# DXP.net
KiCad netlist of a schematic drawn in Altium Designer
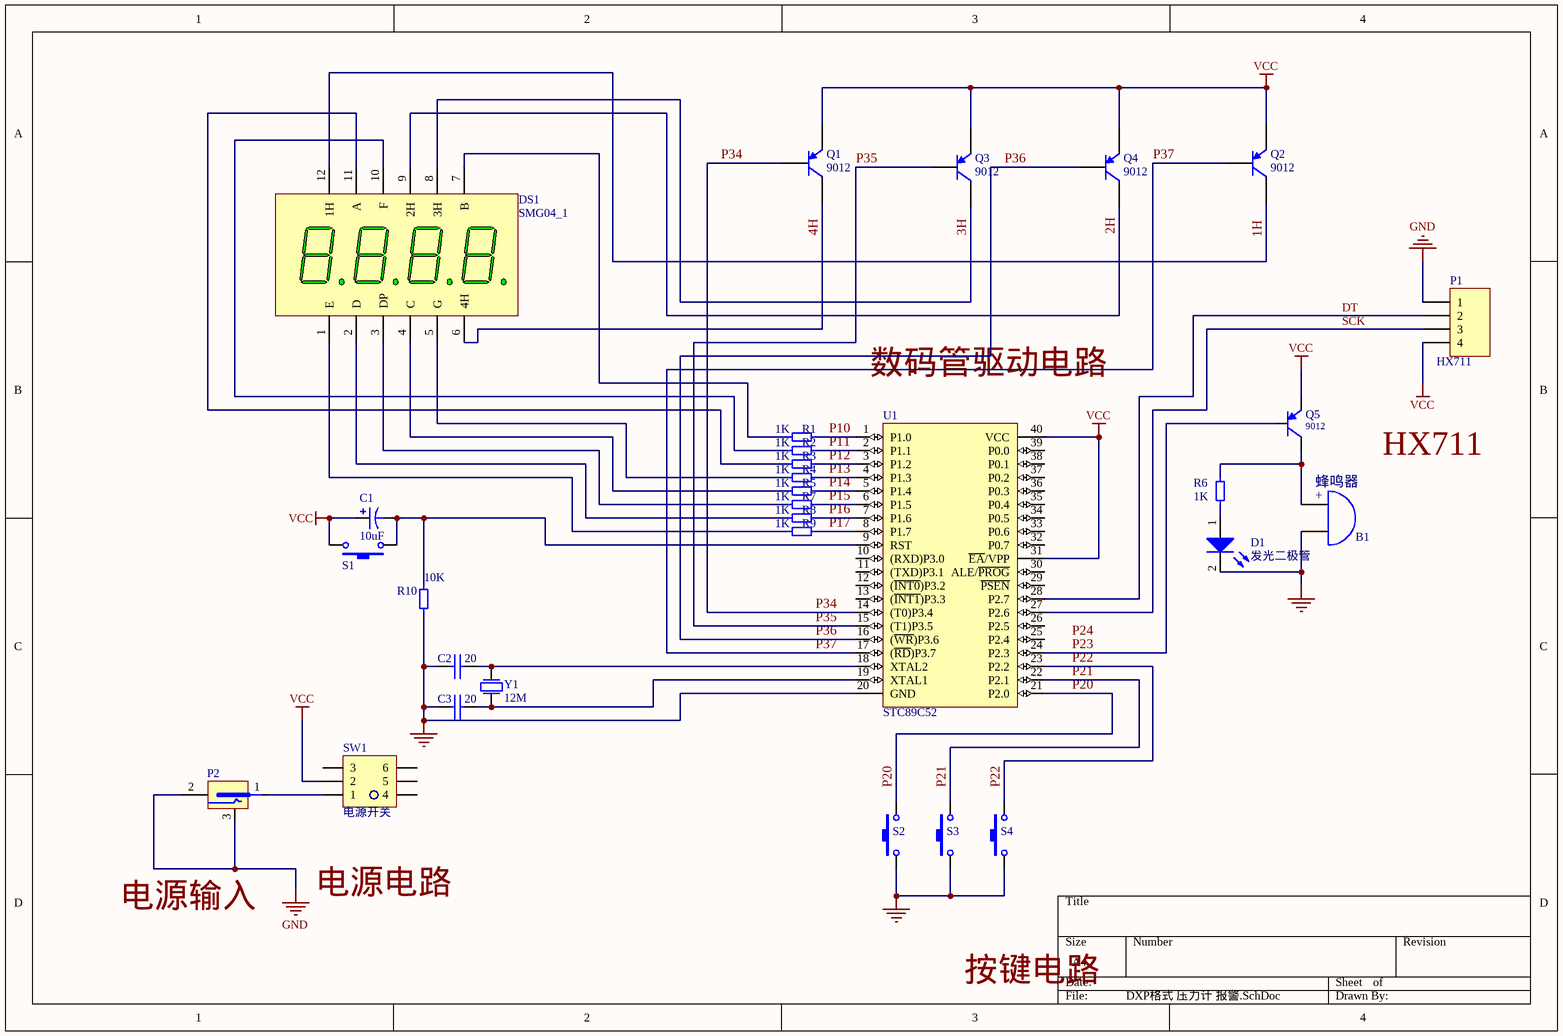
[diagram p0: DXP格式 压力计 报警.SchDoc]

(export (version "E")
  (design (tool "Eeschema 10.0.6"))
  (components
    (comp (ref "B1")
      (value "蜂鸣器")
      (footprint "Bett")
      (description "Bell")
      (libsource (lib "*") (part "BELL"))
    )
    (comp (ref "C1")
      (value "10uF")
      (footprint "C_10")
      (description "Polarized Capacitor (Radial)")
      (fields (field (name "PUBLISHER") "Altium Limited"))
      (libsource (lib "*") (part "Cap Pol1"))
    )
    (comp (ref "C2") (value "20") (footprint "CAP CP") (description "电容") (libsource (lib "*") (part "CAP")))
    (comp (ref "C3") (value "20") (footprint "CAP CP") (description "电容") (libsource (lib "*") (part "CAP")))
    (comp (ref "D1") (value "发光二极管") (footprint "LED直插") (libsource (lib "*") (part "D")))
    (comp (ref "DS1") (value "SMG04_1") (footprint "SMG04") (libsource (lib "*") (part "SMG04_1")))
    (comp (ref "P1")
      (value "HX711")
      (footprint "HX711")
      (description "Header, 4-Pin")
      (fields (field (name "PUBLISHER") "Altium Limited"))
      (libsource (lib "Miscellaneous Connectors") (part "Header 4"))
    )
    (comp (ref "P2") (value "电源输入") (footprint "DC2.1") (libsource (lib "我自己的") (part "POWER")))
    (comp (ref "Q1")
      (value "9012")
      (footprint "s三极管直插")
      (description "PNP General Purpose Amplifier")
      (fields (field (name "PUBLISHER") "Altium Limited"))
      (libsource (lib "*") (part "2N3906"))
    )
    (comp (ref "Q2")
      (value "9012")
      (footprint "s三极管直插")
      (description "PNP General Purpose Amplifier")
      (fields (field (name "PUBLISHER") "Altium Limited"))
      (libsource (lib "*") (part "2N3906"))
    )
    (comp (ref "Q3")
      (value "9012")
      (footprint "s三极管直插")
      (description "PNP General Purpose Amplifier")
      (fields (field (name "PUBLISHER") "Altium Limited"))
      (libsource (lib "*") (part "2N3906"))
    )
    (comp (ref "Q4")
      (value "9012")
      (footprint "s三极管直插")
      (description "PNP General Purpose Amplifier")
      (fields (field (name "PUBLISHER") "Altium Limited"))
      (libsource (lib "*") (part "2N3906"))
    )
    (comp (ref "Q5")
      (value "9012")
      (footprint "s三极管直插")
      (description "PNP General Purpose Amplifier")
      (fields (field (name "PUBLISHER") "Altium Limited"))
      (libsource (lib "") (part "2N3906_1"))
    )
    (comp (ref "R1") (value "1K") (footprint "AXIAL0.3") (libsource (lib "*") (part "RES2")))
    (comp (ref "R2") (value "1K") (footprint "AXIAL0.3") (libsource (lib "*") (part "RES2")))
    (comp (ref "R3") (value "1K") (footprint "AXIAL0.3") (libsource (lib "*") (part "RES2")))
    (comp (ref "R4") (value "1K") (footprint "AXIAL0.3") (libsource (lib "*") (part "RES2")))
    (comp (ref "R5") (value "1K") (footprint "AXIAL0.3") (libsource (lib "*") (part "RES2")))
    (comp (ref "R6") (value "1K") (footprint "AXIAL0.3") (libsource (lib "*") (part "RES2")))
    (comp (ref "R7") (value "1K") (footprint "AXIAL0.3") (libsource (lib "*") (part "RES2")))
    (comp (ref "R8") (value "1K") (footprint "AXIAL0.3") (libsource (lib "*") (part "RES2")))
    (comp (ref "R9") (value "1K") (footprint "AXIAL0.3") (libsource (lib "*") (part "RES2")))
    (comp (ref "R10") (value "10K") (footprint "AXIAL0.3") (libsource (lib "*") (part "RES2")))
    (comp (ref "S1")
      (value "SW-PB")
      (footprint "key")
      (description "Switch")
      (fields (field (name "PUBLISHER") "Altium Limited"))
      (libsource (lib "*") (part "SW-PB"))
    )
    (comp (ref "S2")
      (value "SW-PB")
      (footprint "key")
      (description "Switch")
      (fields (field (name "PUBLISHER") "Altium Limited"))
      (libsource (lib "*") (part "SW-PB"))
    )
    (comp (ref "S3")
      (value "SW-PB")
      (footprint "key")
      (description "Switch")
      (fields (field (name "PUBLISHER") "Altium Limited"))
      (libsource (lib "*") (part "SW-PB"))
    )
    (comp (ref "S4")
      (value "SW-PB")
      (footprint "key")
      (description "Switch")
      (fields (field (name "PUBLISHER") "Altium Limited"))
      (libsource (lib "*") (part "SW-PB"))
    )
    (comp (ref "SW1") (value "电源开关") (footprint "sw_自锁 1") (libsource (lib "我自己的") (part "SW1")))
    (comp (ref "U1") (value "STC89C52") (footprint "DIP40 - 做板") (libsource (lib "*") (part "U1")))
    (comp (ref "Y1")
      (value "12M")
      (footprint "XTAL")
      (description "Crystal Oscillator")
      (libsource (lib "*") (part "16M"))
    )
  )
  (nets
    (net (code "1") (name "/1H") (class "Default")
      (node (ref "DS1") (pin "12") (pinfunction "1H_12") (pintype "passive"))
      (node (ref "Q2") (pin "3") (pinfunction "C_3") (pintype "passive"))
    )
    (net (code "2") (name "/2H") (class "Default")
      (node (ref "DS1") (pin "9") (pinfunction "2H_9") (pintype "passive"))
      (node (ref "Q4") (pin "3") (pinfunction "C_3") (pintype "passive"))
    )
    (net (code "3") (name "/3H") (class "Default")
      (node (ref "DS1") (pin "8") (pinfunction "3H_8") (pintype "passive"))
      (node (ref "Q3") (pin "3") (pinfunction "C_3") (pintype "passive"))
    )
    (net (code "4") (name "/4H") (class "Default")
      (node (ref "DS1") (pin "6") (pinfunction "4H_6") (pintype "passive"))
      (node (ref "Q1") (pin "3") (pinfunction "C_3") (pintype "passive"))
    )
    (net (code "5") (name "/DT") (class "Default")
      (node (ref "P1") (pin "2") (pinfunction "2_2") (pintype "passive"))
      (node (ref "U1") (pin "28") (pinfunction "P2.7_28") (pintype "bidirectional"))
    )
    (net (code "7") (name "/P10") (class "Default")
      (node (ref "R1") (pin "2") (pinfunction "2_2") (pintype "passive"))
      (node (ref "U1") (pin "1") (pinfunction "P1.0_1") (pintype "bidirectional"))
    )
    (net (code "8") (name "/P11") (class "Default")
      (node (ref "R2") (pin "2") (pinfunction "2_2") (pintype "passive"))
      (node (ref "U1") (pin "2") (pinfunction "P1.1_2") (pintype "bidirectional"))
    )
    (net (code "9") (name "/P12") (class "Default")
      (node (ref "R3") (pin "2") (pinfunction "2_2") (pintype "passive"))
      (node (ref "U1") (pin "3") (pinfunction "P1.2_3") (pintype "bidirectional"))
    )
    (net (code "10") (name "/P13") (class "Default")
      (node (ref "R4") (pin "2") (pinfunction "2_2") (pintype "passive"))
      (node (ref "U1") (pin "4") (pinfunction "P1.3_4") (pintype "bidirectional"))
    )
    (net (code "11") (name "/P14") (class "Default")
      (node (ref "R5") (pin "2") (pinfunction "2_2") (pintype "passive"))
      (node (ref "U1") (pin "5") (pinfunction "P1.4_5") (pintype "bidirectional"))
    )
    (net (code "12") (name "/P15") (class "Default")
      (node (ref "R7") (pin "2") (pinfunction "2_2") (pintype "passive"))
      (node (ref "U1") (pin "6") (pinfunction "P1.5_6") (pintype "bidirectional"))
    )
    (net (code "13") (name "/P16") (class "Default")
      (node (ref "R8") (pin "2") (pinfunction "2_2") (pintype "passive"))
      (node (ref "U1") (pin "7") (pinfunction "P1.6_7") (pintype "bidirectional"))
    )
    (net (code "14") (name "/P17") (class "Default")
      (node (ref "R9") (pin "2") (pinfunction "2_2") (pintype "passive"))
      (node (ref "U1") (pin "8") (pinfunction "P1.7_8") (pintype "bidirectional"))
    )
    (net (code "15") (name "/P20") (class "Default")
      (node (ref "S2") (pin "2") (pinfunction "2_2") (pintype "passive"))
      (node (ref "U1") (pin "21") (pinfunction "P2.0_21") (pintype "bidirectional"))
    )
    (net (code "16") (name "/P21") (class "Default")
      (node (ref "S3") (pin "2") (pinfunction "2_2") (pintype "passive"))
      (node (ref "U1") (pin "22") (pinfunction "P2.1_22") (pintype "bidirectional"))
    )
    (net (code "17") (name "/P22") (class "Default")
      (node (ref "S4") (pin "2") (pinfunction "2_2") (pintype "passive"))
      (node (ref "U1") (pin "23") (pinfunction "P2.2_23") (pintype "bidirectional"))
    )
    (net (code "18") (name "/P23") (class "Default")
      (node (ref "Q5") (pin "2") (pinfunction "B_2") (pintype "passive"))
      (node (ref "U1") (pin "24") (pinfunction "P2.3_24") (pintype "bidirectional"))
    )
    (net (code "20") (name "/P34") (class "Default")
      (node (ref "Q1") (pin "2") (pinfunction "B_2") (pintype "passive"))
      (node (ref "U1") (pin "14") (pinfunction "(T0)P3.4_14") (pintype "bidirectional"))
    )
    (net (code "21") (name "/P35") (class "Default")
      (node (ref "Q3") (pin "2") (pinfunction "B_2") (pintype "passive"))
      (node (ref "U1") (pin "15") (pinfunction "(T1)P3.5_15") (pintype "bidirectional"))
    )
    (net (code "22") (name "/P36") (class "Default")
      (node (ref "Q4") (pin "2") (pinfunction "B_2") (pintype "passive"))
      (node (ref "U1") (pin "16") (pinfunction "(~{WR})P3.6_16") (pintype "bidirectional"))
    )
    (net (code "23") (name "/P37") (class "Default")
      (node (ref "Q2") (pin "2") (pinfunction "B_2") (pintype "passive"))
      (node (ref "U1") (pin "17") (pinfunction "(~{RD})P3.7_17") (pintype "bidirectional"))
    )
    (net (code "24") (name "/SCK") (class "Default")
      (node (ref "P1") (pin "3") (pinfunction "3_3") (pintype "passive"))
      (node (ref "U1") (pin "27") (pinfunction "P2.6_27") (pintype "bidirectional"))
    )
    (net (code "29") (name "GND") (class "Default")
      (node (ref "B1") (pin "2") (pinfunction "B_2") (pintype "passive"))
      (node (ref "C2") (pin "1") (pinfunction "1_1") (pintype "passive"))
      (node (ref "C3") (pin "1") (pinfunction "1_1") (pintype "passive"))
      (node (ref "D1") (pin "2") (pintype "passive"))
      (node (ref "P1") (pin "1") (pinfunction "1_1") (pintype "passive"))
      (node (ref "P2") (pin "2") (pintype "passive"))
      (node (ref "P2") (pin "3") (pintype "passive"))
      (node (ref "R10") (pin "1") (pinfunction "1_1") (pintype "passive"))
      (node (ref "S2") (pin "1") (pinfunction "1_1") (pintype "passive"))
      (node (ref "S3") (pin "1") (pinfunction "1_1") (pintype "passive"))
      (node (ref "S4") (pin "1") (pinfunction "1_1") (pintype "passive"))
      (node (ref "U1") (pin "20") (pinfunction "GND_20") (pintype "power_in"))
    )
    (net (code "30") (name "Net-(B1-A)") (class "Default")
      (node (ref "B1") (pin "1") (pinfunction "A_1") (pintype "passive"))
      (node (ref "Q5") (pin "3") (pinfunction "C_3") (pintype "passive"))
      (node (ref "R6") (pin "1") (pinfunction "1_1") (pintype "passive"))
    )
    (net (code "31") (name "Net-(D1-Pad1)") (class "Default")
      (node (ref "D1") (pin "1") (pintype "passive"))
      (node (ref "R6") (pin "2") (pinfunction "2_2") (pintype "passive"))
    )
    (net (code "32") (name "Net-(DS1-A)") (class "Default")
      (node (ref "DS1") (pin "11") (pinfunction "A_11") (pintype "passive"))
      (node (ref "R3") (pin "1") (pinfunction "1_1") (pintype "passive"))
    )
    (net (code "33") (name "Net-(DS1-B)") (class "Default")
      (node (ref "DS1") (pin "7") (pinfunction "B_7") (pintype "passive"))
      (node (ref "R1") (pin "1") (pinfunction "1_1") (pintype "passive"))
    )
    (net (code "34") (name "Net-(DS1-C)") (class "Default")
      (node (ref "DS1") (pin "4") (pinfunction "C_4") (pintype "passive"))
      (node (ref "R5") (pin "1") (pinfunction "1_1") (pintype "passive"))
    )
    (net (code "35") (name "Net-(DS1-D)") (class "Default")
      (node (ref "DS1") (pin "2") (pinfunction "D_2") (pintype "passive"))
      (node (ref "R8") (pin "1") (pinfunction "1_1") (pintype "passive"))
    )
    (net (code "36") (name "Net-(DS1-DP)") (class "Default")
      (node (ref "DS1") (pin "3") (pinfunction "DP_3") (pintype "passive"))
      (node (ref "R7") (pin "1") (pinfunction "1_1") (pintype "passive"))
    )
    (net (code "37") (name "Net-(DS1-E)") (class "Default")
      (node (ref "DS1") (pin "1") (pinfunction "E_1") (pintype "passive"))
      (node (ref "R9") (pin "1") (pinfunction "1_1") (pintype "passive"))
    )
    (net (code "38") (name "Net-(DS1-F)") (class "Default")
      (node (ref "DS1") (pin "10") (pinfunction "F_10") (pintype "passive"))
      (node (ref "R2") (pin "1") (pinfunction "1_1") (pintype "passive"))
    )
    (net (code "39") (name "Net-(DS1-G)") (class "Default")
      (node (ref "DS1") (pin "5") (pinfunction "G_5") (pintype "passive"))
      (node (ref "R4") (pin "1") (pinfunction "1_1") (pintype "passive"))
    )
    (net (code "40") (name "Net-(P2-Pad1)") (class "Default")
      (node (ref "P2") (pin "1") (pintype "passive"))
      (node (ref "SW1") (pin "1") (pinfunction "1_1") (pintype "passive"))
    )
    (net (code "41") (name "Net-(U1-RST)") (class "Default")
      (node (ref "C1") (pin "2") (pinfunction "2_2") (pintype "passive"))
      (node (ref "R10") (pin "2") (pinfunction "2_2") (pintype "passive"))
      (node (ref "S1") (pin "1") (pinfunction "1_1") (pintype "passive"))
      (node (ref "U1") (pin "9") (pinfunction "RST_9") (pintype "bidirectional"))
    )
    (net (code "42") (name "Net-(U1-XTAL1)") (class "Default")
      (node (ref "C3") (pin "2") (pinfunction "2_2") (pintype "passive"))
      (node (ref "U1") (pin "19") (pinfunction "XTAL1_19") (pintype "bidirectional"))
      (node (ref "Y1") (pin "2") (pinfunction "P2_2") (pintype "passive"))
    )
    (net (code "43") (name "Net-(U1-XTAL2)") (class "Default")
      (node (ref "C2") (pin "2") (pinfunction "2_2") (pintype "passive"))
      (node (ref "U1") (pin "18") (pinfunction "XTAL2_18") (pintype "bidirectional"))
      (node (ref "Y1") (pin "1") (pinfunction "P1_1") (pintype "passive"))
    )
    (net (code "44") (name "VCC") (class "Default")
      (node (ref "C1") (pin "1") (pinfunction "1_1") (pintype "passive"))
      (node (ref "P1") (pin "4") (pinfunction "4_4") (pintype "passive"))
      (node (ref "Q1") (pin "1") (pinfunction "E_1") (pintype "passive"))
      (node (ref "Q2") (pin "1") (pinfunction "E_1") (pintype "passive"))
      (node (ref "Q3") (pin "1") (pinfunction "E_1") (pintype "passive"))
      (node (ref "Q4") (pin "1") (pinfunction "E_1") (pintype "passive"))
      (node (ref "Q5") (pin "1") (pinfunction "E_1") (pintype "passive"))
      (node (ref "S1") (pin "2") (pinfunction "2_2") (pintype "passive"))
      (node (ref "SW1") (pin "2") (pinfunction "2_2") (pintype "passive"))
      (node (ref "U1") (pin "31") (pinfunction "~{EA}/VPP_31") (pintype "power_in"))
      (node (ref "U1") (pin "40") (pinfunction "VCC_40") (pintype "power_in"))
    )
    (net (code "45") (name "unconnected-(SW1-Pad3)") (class "Default")
      (node (ref "SW1") (pin "3") (pinfunction "3_3") (pintype "passive"))
    )
    (net (code "46") (name "unconnected-(SW1-Pad4)") (class "Default")
      (node (ref "SW1") (pin "4") (pinfunction "4_4") (pintype "passive"))
    )
    (net (code "47") (name "unconnected-(SW1-Pad5)") (class "Default")
      (node (ref "SW1") (pin "5") (pinfunction "5_5") (pintype "passive"))
    )
    (net (code "48") (name "unconnected-(SW1-Pad6)") (class "Default")
      (node (ref "SW1") (pin "6") (pinfunction "6_6") (pintype "passive"))
    )
    (net (code "49") (name "unconnected-(U1-(RXD)P3.0-Pad10)") (class "Default")
      (node (ref "U1") (pin "10") (pinfunction "(RXD)P3.0_10") (pintype "bidirectional"))
    )
    (net (code "50") (name "unconnected-(U1-(TXD)P3.1-Pad11)") (class "Default")
      (node (ref "U1") (pin "11") (pinfunction "(TXD)P3.1_11") (pintype "bidirectional"))
    )
    (net (code "51") (name "unconnected-(U1-(~{INT0})P3.2-Pad12)") (class "Default")
      (node (ref "U1") (pin "12") (pinfunction "(~{INT0})P3.2_12") (pintype "bidirectional"))
    )
    (net (code "52") (name "unconnected-(U1-(~{INT1})P3.3-Pad13)") (class "Default")
      (node (ref "U1") (pin "13") (pinfunction "(~{INT1})P3.3_13") (pintype "bidirectional"))
    )
    (net (code "53") (name "unconnected-(U1-ALE{slash}~{PROG}-Pad30)") (class "Default")
      (node (ref "U1") (pin "30") (pinfunction "ALE/~{PROG}_30") (pintype "bidirectional"))
    )
    (net (code "54") (name "unconnected-(U1-P0.0-Pad39)") (class "Default")
      (node (ref "U1") (pin "39") (pinfunction "P0.0_39") (pintype "bidirectional"))
    )
    (net (code "55") (name "unconnected-(U1-P0.1-Pad38)") (class "Default")
      (node (ref "U1") (pin "38") (pinfunction "P0.1_38") (pintype "bidirectional"))
    )
    (net (code "56") (name "unconnected-(U1-P0.2-Pad37)") (class "Default")
      (node (ref "U1") (pin "37") (pinfunction "P0.2_37") (pintype "bidirectional"))
    )
    (net (code "57") (name "unconnected-(U1-P0.3-Pad36)") (class "Default")
      (node (ref "U1") (pin "36") (pinfunction "P0.3_36") (pintype "bidirectional"))
    )
    (net (code "58") (name "unconnected-(U1-P0.4-Pad35)") (class "Default")
      (node (ref "U1") (pin "35") (pinfunction "P0.4_35") (pintype "bidirectional"))
    )
    (net (code "59") (name "unconnected-(U1-P0.5-Pad34)") (class "Default")
      (node (ref "U1") (pin "34") (pinfunction "P0.5_34") (pintype "bidirectional"))
    )
    (net (code "60") (name "unconnected-(U1-P0.6-Pad33)") (class "Default")
      (node (ref "U1") (pin "33") (pinfunction "P0.6_33") (pintype "bidirectional"))
    )
    (net (code "61") (name "unconnected-(U1-P0.7-Pad32)") (class "Default")
      (node (ref "U1") (pin "32") (pinfunction "P0.7_32") (pintype "bidirectional"))
    )
    (net (code "62") (name "unconnected-(U1-P2.4-Pad25)") (class "Default")
      (node (ref "U1") (pin "25") (pinfunction "P2.4_25") (pintype "bidirectional"))
    )
    (net (code "63") (name "unconnected-(U1-P2.5-Pad26)") (class "Default")
      (node (ref "U1") (pin "26") (pinfunction "P2.5_26") (pintype "bidirectional"))
    )
    (net (code "64") (name "unconnected-(U1-~{PSEN}-Pad29)") (class "Default")
      (node (ref "U1") (pin "29") (pinfunction "~{PSEN}_29") (pintype "bidirectional"))
    )
  )
)
